# sample.net
KiCad netlist of a schematic drawn in EAGLE
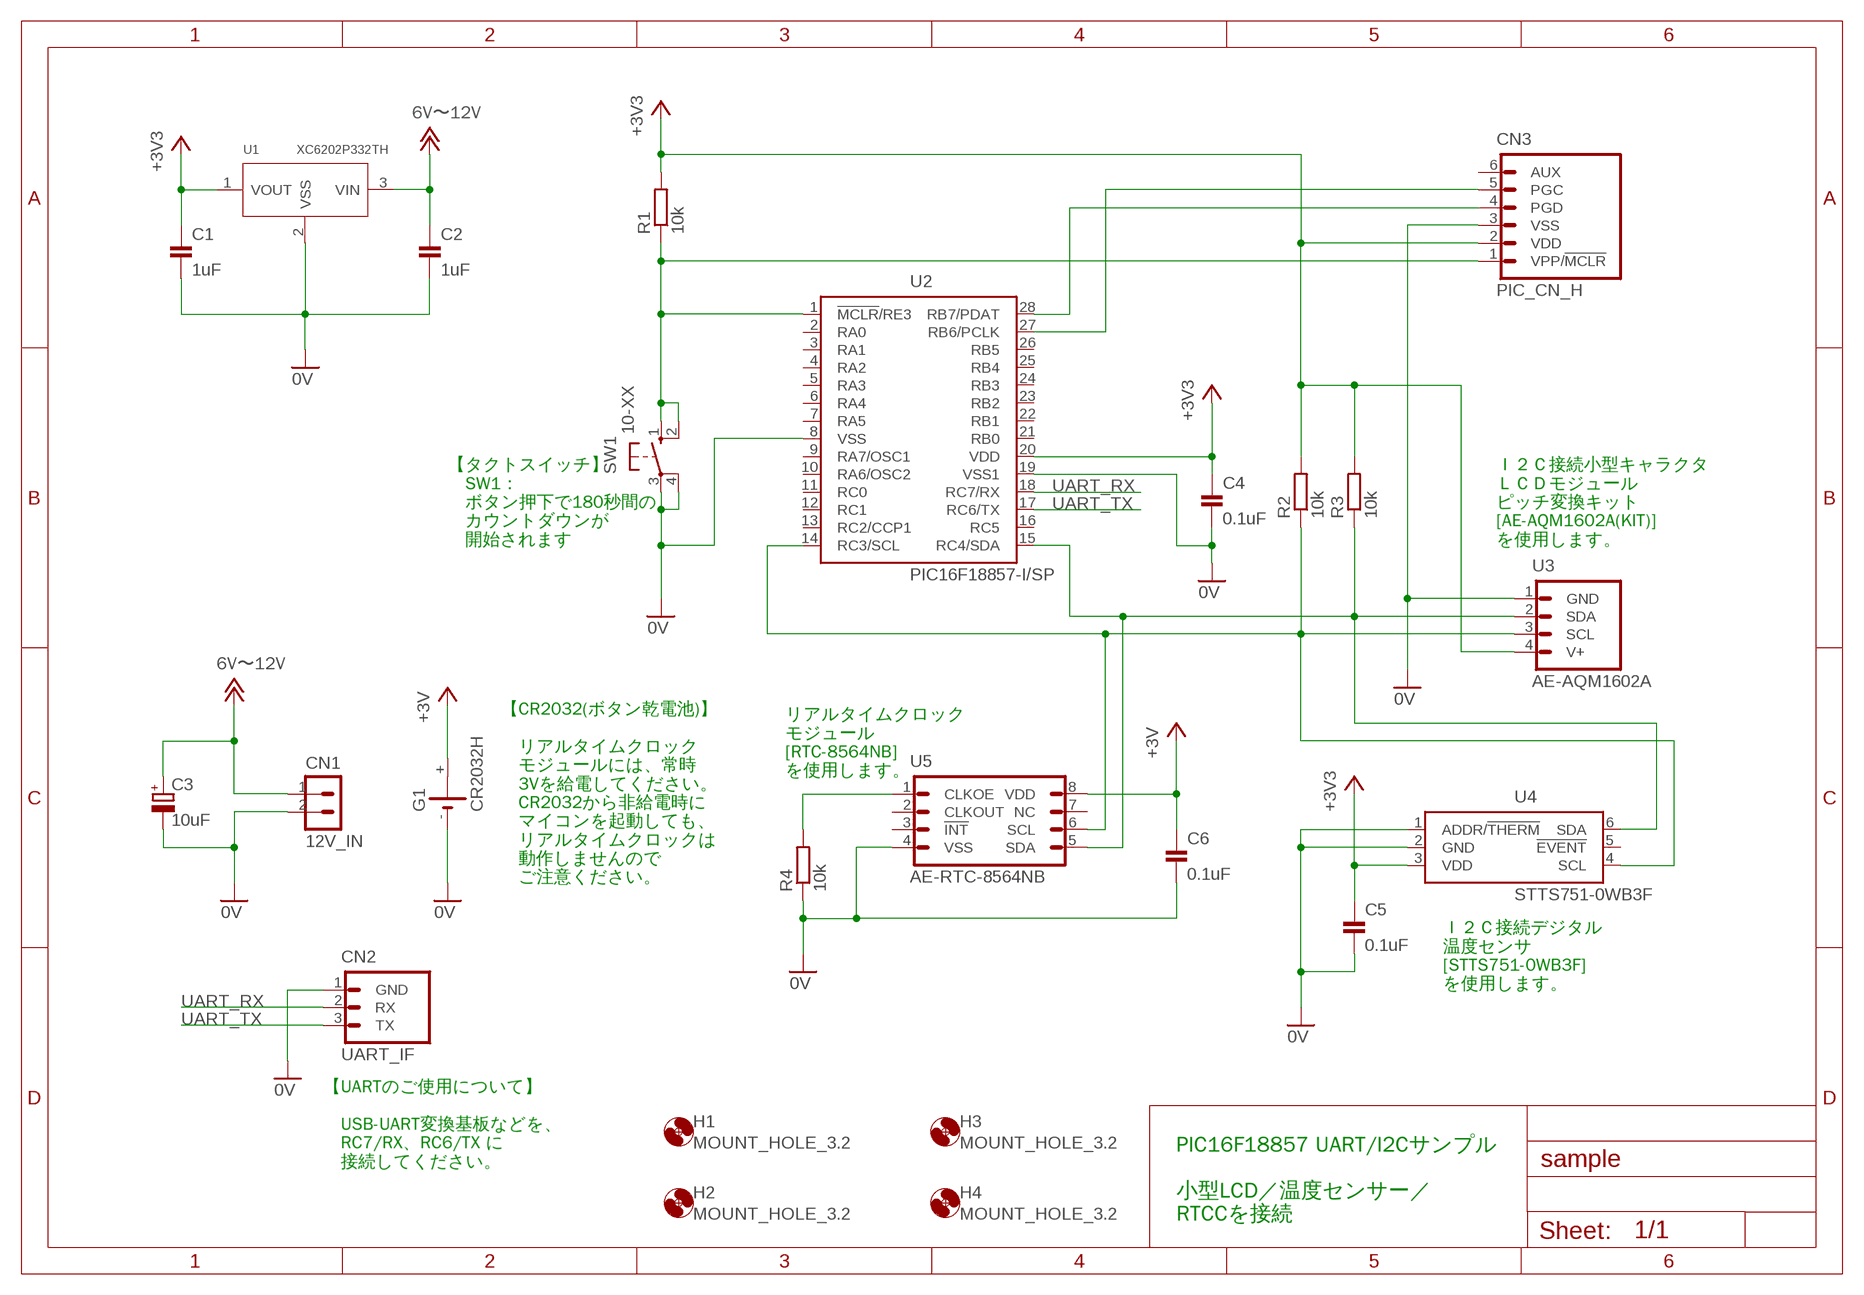
[diagram p0: schematic, sheet 1]

(export (version "E")
  (design (tool "Eeschema 10.0.6"))
  (components
    (comp (ref "C1")
      (value "1uF")
      (footprint "eagle-import:CAP_200MIL")
      (libsource (lib "eagle-import") (part "CAP_200MIL"))
    )
    (comp (ref "C2")
      (value "1uF")
      (footprint "eagle-import:CAP_200MIL")
      (libsource (lib "eagle-import") (part "CAP_200MIL"))
    )
    (comp (ref "C3")
      (value "10uF")
      (footprint "eagle-import:ELECAP_200MIL")
      (libsource (lib "eagle-import") (part "ELECAP_200MIL"))
    )
    (comp (ref "C4")
      (value "0.1uF")
      (footprint "eagle-import:CAP_200MIL")
      (libsource (lib "eagle-import") (part "CAP_200MIL"))
    )
    (comp (ref "C5")
      (value "0.1uF")
      (footprint "eagle-import:CAP_200MIL")
      (libsource (lib "eagle-import") (part "CAP_200MIL"))
    )
    (comp (ref "C6")
      (value "0.1uF")
      (footprint "eagle-import:CAP_200MIL")
      (libsource (lib "eagle-import") (part "CAP_200MIL"))
    )
    (comp (ref "CN1")
      (value "12V_IN")
      (footprint "eagle-import:HEADER_L_2PIN")
      (libsource (lib "eagle-import") (part "CONN_2PIN-L"))
    )
    (comp (ref "CN2")
      (value "UART_IF")
      (footprint "eagle-import:UART_IF_3PIN")
      (libsource (lib "eagle-import") (part "UART_IF"))
    )
    (comp (ref "CN3")
      (value "PIC_CN_H")
      (footprint "eagle-import:HEADER_6PIN")
      (libsource (lib "eagle-import") (part "PIC_CN_H"))
    )
    (comp (ref "G1")
      (value "CR2032H")
      (footprint "eagle-import:CR2032H")
      (libsource (lib "eagle-import") (part "CR2032H"))
    )
    (comp (ref "H1")
      (value "MOUNT_HOLE_3.2")
      (footprint "eagle-import:3,2")
      (libsource (lib "eagle-import") (part "MOUNT_HOLE_3.2"))
    )
    (comp (ref "H2")
      (value "MOUNT_HOLE_3.2")
      (footprint "eagle-import:3,2")
      (libsource (lib "eagle-import") (part "MOUNT_HOLE_3.2"))
    )
    (comp (ref "H3")
      (value "MOUNT_HOLE_3.2")
      (footprint "eagle-import:3,2")
      (libsource (lib "eagle-import") (part "MOUNT_HOLE_3.2"))
    )
    (comp (ref "H4")
      (value "MOUNT_HOLE_3.2")
      (footprint "eagle-import:3,2")
      (libsource (lib "eagle-import") (part "MOUNT_HOLE_3.2"))
    )
    (comp (ref "R1")
      (value "10k")
      (footprint "eagle-import:RESISTOR_0207_300MIL")
      (libsource (lib "eagle-import") (part "RESISTOR_300MIL"))
    )
    (comp (ref "R2")
      (value "10k")
      (footprint "eagle-import:RESISTOR_0207_300MIL")
      (libsource (lib "eagle-import") (part "RESISTOR_300MIL"))
    )
    (comp (ref "R3")
      (value "10k")
      (footprint "eagle-import:RESISTOR_0207_300MIL")
      (libsource (lib "eagle-import") (part "RESISTOR_300MIL"))
    )
    (comp (ref "R4")
      (value "10k")
      (footprint "eagle-import:RESISTOR_0207_300MIL")
      (libsource (lib "eagle-import") (part "RESISTOR_300MIL"))
    )
    (comp (ref "SW1")
      (value "10-XX")
      (footprint "eagle-import:B3F-10XX")
      (libsource (lib "eagle-import") (part "10-XX"))
    )
    (comp (ref "U1")
      (value "XC6202P332TH")
      (footprint "eagle-import:TO92-LINE")
      (libsource (lib "eagle-import") (part "XC6202P332TH"))
    )
    (comp (ref "U2")
      (value "PIC16F18857-I/SP")
      (footprint "eagle-import:DIL28-3")
      (libsource (lib "eagle-import") (part "PIC16F18857-I/SP"))
    )
    (comp (ref "U3")
      (value "AE-AQM1602A")
      (footprint "eagle-import:AE-AQM1602A")
      (libsource (lib "eagle-import") (part "AE-AQM1602A"))
    )
    (comp (ref "U4")
      (value "STTS751-0WB3F")
      (footprint "eagle-import:SOT23-6L")
      (libsource (lib "eagle-import") (part "STTS751-0WB3F"))
    )
    (comp (ref "U5")
      (value "AE-RTC-8564NB")
      (footprint "eagle-import:DIL8_AE-RTC-8564NB")
      (libsource (lib "eagle-import") (part "AE-RTC-8564NB"))
    )
  )
  (nets
    (net (code "1") (name "+3V") (class "Default")
      (node (ref "C6") (pin "1") (pinfunction "1_1") (pintype "passive"))
      (node (ref "G1") (pin "+") (pinfunction "+_+") (pintype "passive"))
      (node (ref "U5") (pin "8") (pinfunction "VDD_8") (pintype "passive"))
    )
    (net (code "2") (name "+3V3") (class "Default")
      (node (ref "C1") (pin "1") (pinfunction "1_1") (pintype "passive"))
      (node (ref "C4") (pin "1") (pinfunction "1_1") (pintype "passive"))
      (node (ref "C5") (pin "1") (pinfunction "1_1") (pintype "passive"))
      (node (ref "CN3") (pin "2") (pinfunction "VDD_2") (pintype "passive"))
      (node (ref "R1") (pin "2") (pinfunction "2_2") (pintype "passive"))
      (node (ref "R2") (pin "2") (pinfunction "2_2") (pintype "passive"))
      (node (ref "R3") (pin "2") (pinfunction "2_2") (pintype "passive"))
      (node (ref "U1") (pin "1") (pinfunction "VOUT_1") (pintype "passive"))
      (node (ref "U2") (pin "20") (pinfunction "VDD_20") (pintype "passive"))
      (node (ref "U3") (pin "4") (pinfunction "V+_4") (pintype "passive"))
      (node (ref "U4") (pin "3") (pinfunction "VDD_3") (pintype "passive"))
    )
    (net (code "3") (name "/UART_RX") (class "Default")
      (node (ref "CN2") (pin "2") (pinfunction "RX_2") (pintype "bidirectional"))
      (node (ref "U2") (pin "18") (pinfunction "RC7/RX_18") (pintype "bidirectional"))
    )
    (net (code "4") (name "/UART_TX") (class "Default")
      (node (ref "CN2") (pin "3") (pinfunction "TX_3") (pintype "bidirectional"))
      (node (ref "U2") (pin "17") (pinfunction "RC6/TX_17") (pintype "bidirectional"))
    )
    (net (code "5") (name "0V") (class "Default")
      (node (ref "C1") (pin "2") (pinfunction "2_2") (pintype "passive"))
      (node (ref "C2") (pin "2") (pinfunction "2_2") (pintype "passive"))
      (node (ref "C3") (pin "-") (pinfunction "-_-") (pintype "passive"))
      (node (ref "C4") (pin "2") (pinfunction "2_2") (pintype "passive"))
      (node (ref "C5") (pin "2") (pinfunction "2_2") (pintype "passive"))
      (node (ref "C6") (pin "2") (pinfunction "2_2") (pintype "passive"))
      (node (ref "CN1") (pin "2") (pinfunction "2_2") (pintype "passive"))
      (node (ref "CN2") (pin "1") (pinfunction "GND_1") (pintype "passive"))
      (node (ref "CN3") (pin "3") (pinfunction "VSS_3") (pintype "passive"))
      (node (ref "G1") (pin "-") (pinfunction "-_-") (pintype "passive"))
      (node (ref "R4") (pin "1") (pinfunction "1_1") (pintype "passive"))
      (node (ref "SW1") (pin "3") (pinfunction "P_3") (pintype "passive"))
      (node (ref "SW1") (pin "4") (pinfunction "P1_4") (pintype "passive"))
      (node (ref "U1") (pin "2") (pinfunction "VSS_2") (pintype "passive"))
      (node (ref "U2") (pin "19") (pinfunction "VSS1_19") (pintype "passive"))
      (node (ref "U2") (pin "8") (pinfunction "VSS_8") (pintype "passive"))
      (node (ref "U3") (pin "1") (pinfunction "GND_1") (pintype "passive"))
      (node (ref "U4") (pin "1") (pinfunction "ADDR/~{THERM}_1") (pintype "bidirectional"))
      (node (ref "U4") (pin "2") (pinfunction "GND_2") (pintype "passive"))
      (node (ref "U5") (pin "4") (pinfunction "VSS_4") (pintype "passive"))
    )
    (net (code "6") (name "6V〜12V") (class "Default")
      (node (ref "C2") (pin "1") (pinfunction "1_1") (pintype "passive"))
      (node (ref "C3") (pin "+") (pinfunction "+_+") (pintype "passive"))
      (node (ref "CN1") (pin "1") (pinfunction "1_1") (pintype "passive"))
      (node (ref "U1") (pin "3") (pinfunction "VIN_3") (pintype "passive"))
    )
    (net (code "7") (name "Net-(CN3-PGC)") (class "Default")
      (node (ref "CN3") (pin "5") (pinfunction "PGC_5") (pintype "input"))
      (node (ref "U2") (pin "27") (pinfunction "RB6/PCLK_27") (pintype "bidirectional"))
    )
    (net (code "8") (name "Net-(CN3-PGD)") (class "Default")
      (node (ref "CN3") (pin "4") (pinfunction "PGD_4") (pintype "bidirectional"))
      (node (ref "U2") (pin "28") (pinfunction "RB7/PDAT_28") (pintype "bidirectional"))
    )
    (net (code "9") (name "Net-(CN3-VPP{slash}~{MCLR})") (class "Default")
      (node (ref "CN3") (pin "1") (pinfunction "VPP/~{MCLR}_1") (pintype "input"))
      (node (ref "R1") (pin "1") (pinfunction "1_1") (pintype "passive"))
      (node (ref "SW1") (pin "1") (pinfunction "S_1") (pintype "passive"))
      (node (ref "SW1") (pin "2") (pinfunction "S1_2") (pintype "passive"))
      (node (ref "U2") (pin "1") (pinfunction "~{MCLR}/RE3_1") (pintype "bidirectional"))
    )
    (net (code "10") (name "Net-(U2-RC3{slash}SCL)") (class "Default")
      (node (ref "R2") (pin "1") (pinfunction "1_1") (pintype "passive"))
      (node (ref "U2") (pin "14") (pinfunction "RC3/SCL_14") (pintype "bidirectional"))
      (node (ref "U3") (pin "3") (pinfunction "SCL_3") (pintype "bidirectional"))
      (node (ref "U4") (pin "4") (pinfunction "SCL_4") (pintype "bidirectional"))
      (node (ref "U5") (pin "6") (pinfunction "SCL_6") (pintype "bidirectional"))
    )
    (net (code "11") (name "Net-(U2-RC4{slash}SDA)") (class "Default")
      (node (ref "R3") (pin "1") (pinfunction "1_1") (pintype "passive"))
      (node (ref "U2") (pin "15") (pinfunction "RC4/SDA_15") (pintype "bidirectional"))
      (node (ref "U3") (pin "2") (pinfunction "SDA_2") (pintype "bidirectional"))
      (node (ref "U4") (pin "6") (pinfunction "SDA_6") (pintype "bidirectional"))
      (node (ref "U5") (pin "5") (pinfunction "SDA_5") (pintype "bidirectional"))
    )
    (net (code "12") (name "Net-(U5-CLKOE)") (class "Default")
      (node (ref "R4") (pin "2") (pinfunction "2_2") (pintype "passive"))
      (node (ref "U5") (pin "1") (pinfunction "CLKOE_1") (pintype "bidirectional"))
    )
    (net (code "13") (name "unconnected-(CN3-AUX-Pad6)") (class "Default")
      (node (ref "CN3") (pin "6") (pinfunction "AUX_6") (pintype "bidirectional"))
    )
    (net (code "14") (name "unconnected-(G1-+-Pad+@1)") (class "Default")
      (node (ref "G1") (pin "+@1") (pinfunction "+_+@1") (pintype "passive"))
    )
    (net (code "15") (name "unconnected-(U2-RA0-Pad2)") (class "Default")
      (node (ref "U2") (pin "2") (pinfunction "RA0_2") (pintype "bidirectional"))
    )
    (net (code "16") (name "unconnected-(U2-RA1-Pad3)") (class "Default")
      (node (ref "U2") (pin "3") (pinfunction "RA1_3") (pintype "bidirectional"))
    )
    (net (code "17") (name "unconnected-(U2-RA2-Pad4)") (class "Default")
      (node (ref "U2") (pin "4") (pinfunction "RA2_4") (pintype "bidirectional"))
    )
    (net (code "18") (name "unconnected-(U2-RA3-Pad5)") (class "Default")
      (node (ref "U2") (pin "5") (pinfunction "RA3_5") (pintype "bidirectional"))
    )
    (net (code "19") (name "unconnected-(U2-RA4-Pad6)") (class "Default")
      (node (ref "U2") (pin "6") (pinfunction "RA4_6") (pintype "bidirectional"))
    )
    (net (code "20") (name "unconnected-(U2-RA5-Pad7)") (class "Default")
      (node (ref "U2") (pin "7") (pinfunction "RA5_7") (pintype "bidirectional"))
    )
    (net (code "21") (name "unconnected-(U2-RA6{slash}OSC2-Pad10)") (class "Default")
      (node (ref "U2") (pin "10") (pinfunction "RA6/OSC2_10") (pintype "bidirectional"))
    )
    (net (code "22") (name "unconnected-(U2-RA7{slash}OSC1-Pad9)") (class "Default")
      (node (ref "U2") (pin "9") (pinfunction "RA7/OSC1_9") (pintype "bidirectional"))
    )
    (net (code "23") (name "unconnected-(U2-RB0-Pad21)") (class "Default")
      (node (ref "U2") (pin "21") (pinfunction "RB0_21") (pintype "bidirectional"))
    )
    (net (code "24") (name "unconnected-(U2-RB1-Pad22)") (class "Default")
      (node (ref "U2") (pin "22") (pinfunction "RB1_22") (pintype "bidirectional"))
    )
    (net (code "25") (name "unconnected-(U2-RB2-Pad23)") (class "Default")
      (node (ref "U2") (pin "23") (pinfunction "RB2_23") (pintype "bidirectional"))
    )
    (net (code "26") (name "unconnected-(U2-RB3-Pad24)") (class "Default")
      (node (ref "U2") (pin "24") (pinfunction "RB3_24") (pintype "bidirectional"))
    )
    (net (code "27") (name "unconnected-(U2-RB4-Pad25)") (class "Default")
      (node (ref "U2") (pin "25") (pinfunction "RB4_25") (pintype "bidirectional"))
    )
    (net (code "28") (name "unconnected-(U2-RB5-Pad26)") (class "Default")
      (node (ref "U2") (pin "26") (pinfunction "RB5_26") (pintype "bidirectional"))
    )
    (net (code "29") (name "unconnected-(U2-RC0-Pad11)") (class "Default")
      (node (ref "U2") (pin "11") (pinfunction "RC0_11") (pintype "bidirectional"))
    )
    (net (code "30") (name "unconnected-(U2-RC1-Pad12)") (class "Default")
      (node (ref "U2") (pin "12") (pinfunction "RC1_12") (pintype "bidirectional"))
    )
    (net (code "31") (name "unconnected-(U2-RC2{slash}CCP1-Pad13)") (class "Default")
      (node (ref "U2") (pin "13") (pinfunction "RC2/CCP1_13") (pintype "bidirectional"))
    )
    (net (code "32") (name "unconnected-(U2-RC5-Pad16)") (class "Default")
      (node (ref "U2") (pin "16") (pinfunction "RC5_16") (pintype "bidirectional"))
    )
    (net (code "33") (name "unconnected-(U4-~{EVENT}-Pad5)") (class "Default")
      (node (ref "U4") (pin "5") (pinfunction "~{EVENT}_5") (pintype "bidirectional"))
    )
    (net (code "34") (name "unconnected-(U5-CLKOUT-Pad2)") (class "Default")
      (node (ref "U5") (pin "2") (pinfunction "CLKOUT_2") (pintype "bidirectional"))
    )
    (net (code "35") (name "unconnected-(U5-NC-Pad7)") (class "Default")
      (node (ref "U5") (pin "7") (pinfunction "NC_7") (pintype "no_connect"))
    )
    (net (code "36") (name "unconnected-(U5-~{INT}-Pad3)") (class "Default")
      (node (ref "U5") (pin "3") (pinfunction "~{INT}_3") (pintype "bidirectional"))
    )
  )
)
